# NGUYENLY.net
KiCad netlist of a schematic drawn in Altium Designer
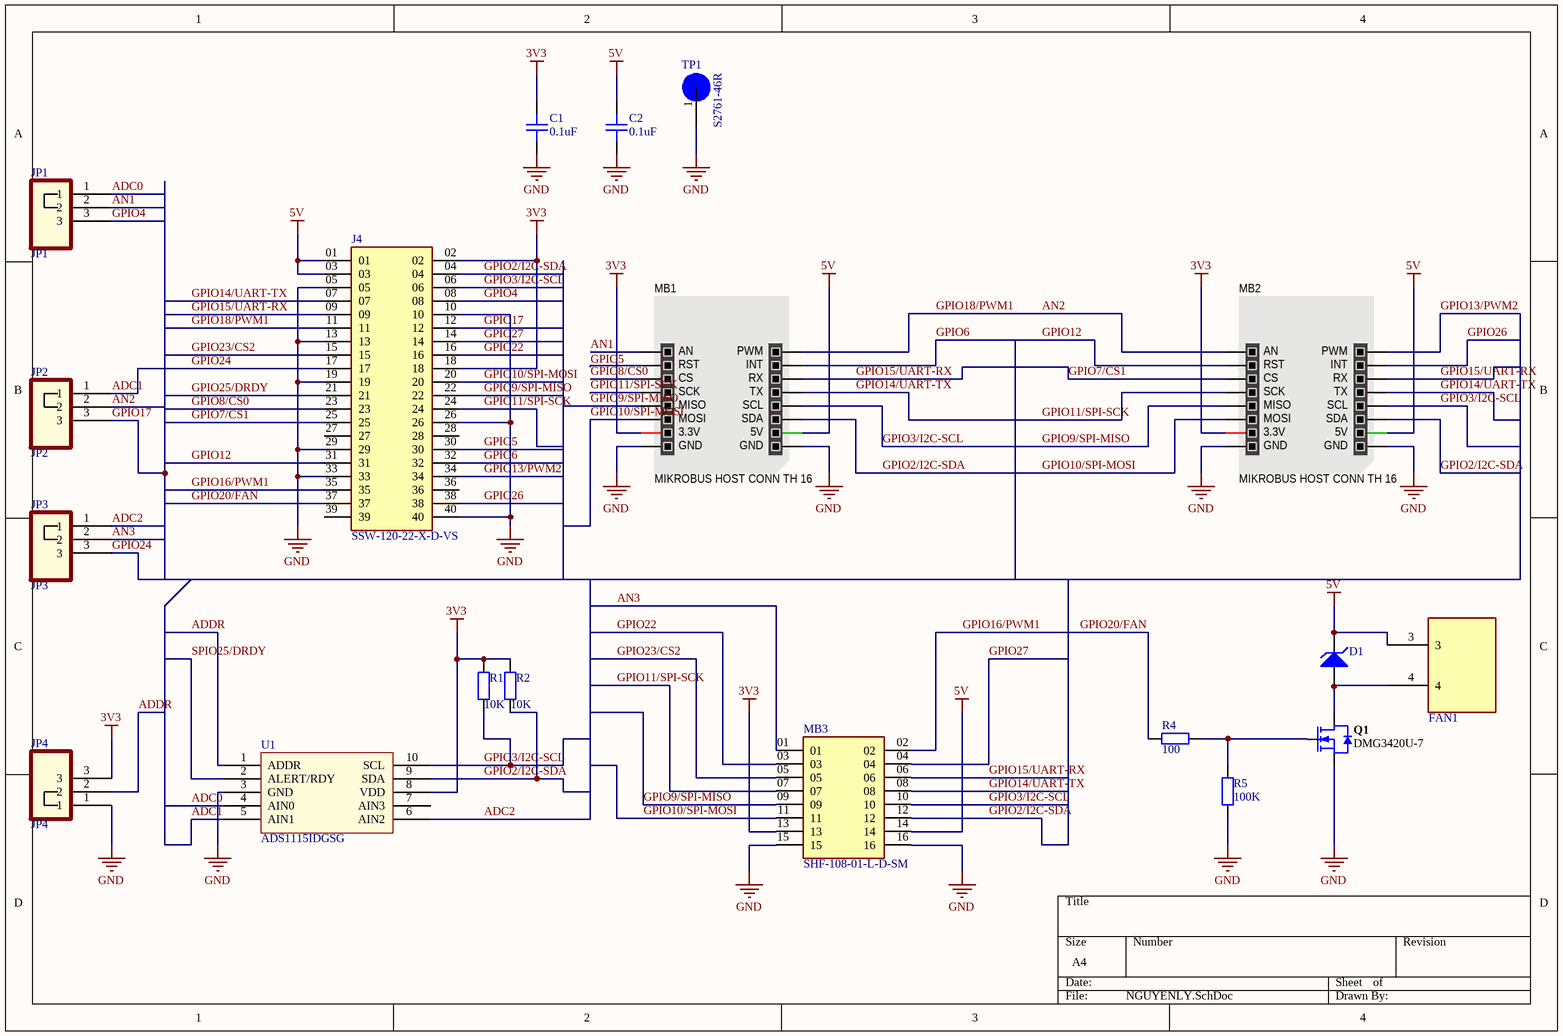
[diagram p0: NGUYENLY.SchDoc]

(export (version "E")
  (design (tool "Eeschema 10.0.6"))
  (components
    (comp (ref "C1")
      (value "0.1uF")
      (footprint "CAPC-0603 (1608)")
      (description "CAP SMD, Not Fill, 0603")
      (libsource (lib "BYTECH_HW_LIB_2019 (1) (1)") (part "CAPC NF 0603"))
    )
    (comp (ref "C2")
      (value "0.1uF")
      (footprint "CAPC-0603 (1608)")
      (description "CAP SMD, Not Fill, 0603")
      (libsource (lib "BYTECH_HW_LIB_2019 (1) (1)") (part "CAPC NF 0603"))
    )
    (comp (ref "D1")
      (value "Diode Zener 3v3 1.5w")
      (footprint "DIODE_DO214AC_SMA")
      (description "DIODE ZENER 3.3V 1.5W SMA, DO-214AC")
      (fields (field (name "MPN") "1SMA5913BT3G"))
      (libsource (lib "BYTECH_HW_LIB_2019 (1) (1)") (part "1SMA5913BT3G; BZG05C3V3TR"))
    )
    (comp (ref "FAN1")
      (value "MF30101V1-1000U-A99")
      (footprint "Sunon_Fans_0_MFG")
      (libsource (lib "UNK_Sunon_Fans_MF30101V1-1000U-A99_eec") (part "MF30101V1-1000U-A99"))
    )
    (comp (ref "J4")
      (value "SSW-120-22-X-D-VS")
      (footprint "SAMTEC_SSW-120-22-X-D-VS")
      (description "40 Position Receptacle Connector Surface Mount")
      (fields (field (name "MF") "Samtec") (field (name "MP") "SSW-120-22-G-D-VS"))
      (libsource (lib "SSW-120-22-X-D-VS") (part "SSW-120-22-X-D-VS"))
    )
    (comp (ref "JP1") (value "JP1") (footprint "PCB") (libsource (lib "JP1") (part "JP")))
    (comp (ref "JP2") (value "JP2") (footprint "PCB") (libsource (lib "JP1") (part "JP")))
    (comp (ref "JP3") (value "JP3") (footprint "PCB") (libsource (lib "JP1") (part "JP")))
    (comp (ref "JP4") (value "JP4") (footprint "PCB") (libsource (lib "") (part "JP_1")))
    (comp (ref "MB1")
      (value "MIKROBUS HOST CONN TH 16")
      (footprint "MIKROBUS HOST SMD 16 - Black")
      (libsource (lib "SOCKET mikroBUS 16 SMD") (part "MIKROBUS HOST CONN"))
    )
    (comp (ref "MB2")
      (value "MIKROBUS HOST CONN TH 16")
      (footprint "MIKROBUS HOST SMD 16 - Black")
      (libsource (lib "SOCKET mikroBUS 16 SMD") (part "MIKROBUS HOST CONN"))
    )
    (comp (ref "MB3")
      (value "SHF-108-01-L-D-SM")
      (footprint "SAMTEC_SHF-108-01-L-D-SM")
      (fields (field (name "MF") "Samtec"))
      (libsource (lib "SHF-108-01-L-D-SM") (part "SHF-108-01-L-D-SM"))
    )
    (comp (ref "Q1")
      (value "DMG3420U-7")
      (footprint "SOT23-123")
      (description "N-channel Enhancement Mode Field-effect Transistor")
      (libsource (lib "TechMT.VN_Lib_Project v2") (part "2N7002"))
    )
    (comp (ref "R1")
      (value "10K")
      (footprint "RESC-0603 (1608)")
      (description "RES SMD, Not Fill, 0603")
      (libsource (lib "") (part "RESC NF 0603_1"))
    )
    (comp (ref "R2")
      (value "10K")
      (footprint "RESC-0603 (1608)")
      (description "RES SMD, Not Fill, 0603")
      (libsource (lib "") (part "RESC NF 0603_1"))
    )
    (comp (ref "R4")
      (value "100")
      (footprint "RESC-0603 (1608)")
      (description "RES SMD, Not Fill, 0603")
      (libsource (lib "") (part "RESC NF 0603_2"))
    )
    (comp (ref "R5")
      (value "100K")
      (footprint "RESC-0603 (1608)")
      (description "RES SMD, Not Fill, 0603")
      (libsource (lib "BYTECH_HW_LIB_2019 (1) (1)") (part "RESC NF 0603"))
    )
    (comp (ref "TP1")
      (value "S2761-46R")
      (footprint "HARWIN_S2761-46R")
      (description "Natural PC Test Point Brass, Tin Plating Surface Mount Mounting Type")
      (fields (field (name "DIGI-KEY_PART_NUMBER") "952-2665-2-ND") (field (name "MF") "Harwin Inc."))
      (libsource (lib "TP1_S2761-46R") (part "S2761-46R"))
    )
    (comp (ref "U1")
      (value "ADS1115IDGSG")
      (footprint "ADS1115IDGSR")
      (libsource (lib "LeNgocHuyHoang") (part "ADS1115IDGSG"))
    )
  )
  (nets
    (net (code "1") (name "/ADC0") (class "Default")
      (node (ref "JP1") (pin "1") (pinfunction "1_1") (pintype "passive"))
      (node (ref "U1") (pin "4") (pinfunction "AIN0_4") (pintype "passive"))
    )
    (net (code "2") (name "/ADC1") (class "Default")
      (node (ref "J4") (pin "17") (pinfunction "17_17") (pintype "passive"))
      (node (ref "JP2") (pin "1") (pinfunction "1_1") (pintype "passive"))
      (node (ref "JP3") (pin "3") (pinfunction "3_3") (pintype "passive"))
      (node (ref "U1") (pin "5") (pinfunction "AIN1_5") (pintype "passive"))
    )
    (net (code "3") (name "/ADC2") (class "Default")
      (node (ref "JP3") (pin "1") (pinfunction "1_1") (pintype "passive"))
      (node (ref "U1") (pin "6") (pinfunction "AIN2_6") (pintype "passive"))
    )
    (net (code "4") (name "/ADDR") (class "Default")
      (node (ref "JP4") (pin "2") (pinfunction "2_2") (pintype "passive"))
      (node (ref "U1") (pin "1") (pinfunction "ADDR_1") (pintype "passive"))
    )
    (net (code "5") (name "/AN1") (class "Default")
      (node (ref "JP1") (pin "2") (pinfunction "2_2") (pintype "passive"))
      (node (ref "MB1") (pin "1") (pinfunction "AN_1") (pintype "passive"))
    )
    (net (code "6") (name "/AN2") (class "Default")
      (node (ref "J4") (pin "11") (pinfunction "11_11") (pintype "passive"))
      (node (ref "J4") (pin "15") (pinfunction "15_15") (pintype "passive"))
      (node (ref "J4") (pin "21") (pinfunction "21_21") (pintype "passive"))
      (node (ref "JP2") (pin "2") (pinfunction "2_2") (pintype "passive"))
      (node (ref "MB1") (pin "16") (pinfunction "PWM_16") (pintype "passive"))
      (node (ref "MB2") (pin "1") (pinfunction "AN_1") (pintype "passive"))
      (node (ref "MB3") (pin "05") (pinfunction "05_05") (pintype "passive"))
    )
    (net (code "7") (name "/AN3") (class "Default")
      (node (ref "JP3") (pin "2") (pinfunction "2_2") (pintype "passive"))
      (node (ref "MB3") (pin "01") (pinfunction "01_01") (pintype "passive"))
    )
    (net (code "8") (name "/GPIO10{slash}SPI-MOSI") (class "Default")
      (node (ref "J4") (pin "04") (pinfunction "04_04") (pintype "passive"))
      (node (ref "J4") (pin "06") (pinfunction "06_06") (pintype "passive"))
      (node (ref "J4") (pin "20") (pinfunction "20_20") (pintype "passive"))
      (node (ref "J4") (pin "22") (pinfunction "22_22") (pintype "passive"))
      (node (ref "MB1") (pin "11") (pinfunction "SDA_11") (pintype "passive"))
      (node (ref "MB1") (pin "12") (pinfunction "SCL_12") (pintype "passive"))
      (node (ref "MB1") (pin "5") (pinfunction "MISO_5") (pintype "passive"))
      (node (ref "MB1") (pin "6") (pinfunction "MOSI_6") (pintype "passive"))
      (node (ref "MB2") (pin "11") (pinfunction "SDA_11") (pintype "passive"))
      (node (ref "MB2") (pin "12") (pinfunction "SCL_12") (pintype "passive"))
      (node (ref "MB2") (pin "5") (pinfunction "MISO_5") (pintype "passive"))
      (node (ref "MB2") (pin "6") (pinfunction "MOSI_6") (pintype "passive"))
      (node (ref "MB3") (pin "09") (pinfunction "09_09") (pintype "passive"))
      (node (ref "MB3") (pin "10") (pinfunction "10_10") (pintype "passive"))
      (node (ref "MB3") (pin "11") (pinfunction "11_11") (pintype "passive"))
      (node (ref "MB3") (pin "12") (pinfunction "12_12") (pintype "passive"))
      (node (ref "R1") (pin "1") (pinfunction "1_1") (pintype "passive"))
      (node (ref "R2") (pin "1") (pinfunction "1_1") (pintype "passive"))
      (node (ref "U1") (pin "10") (pinfunction "SCL_10") (pintype "passive"))
      (node (ref "U1") (pin "9") (pinfunction "SDA_9") (pintype "passive"))
    )
    (net (code "9") (name "/GPIO11{slash}SPI-SCK") (class "Default")
      (node (ref "J4") (pin "07") (pinfunction "07_07") (pintype "passive"))
      (node (ref "J4") (pin "24") (pinfunction "24_24") (pintype "passive"))
      (node (ref "J4") (pin "30") (pinfunction "30_30") (pintype "passive"))
      (node (ref "MB1") (pin "13") (pinfunction "TX_13") (pintype "passive"))
      (node (ref "MB1") (pin "2") (pinfunction "RST_2") (pintype "passive"))
      (node (ref "MB1") (pin "4") (pinfunction "SCK_4") (pintype "passive"))
      (node (ref "MB2") (pin "13") (pinfunction "TX_13") (pintype "passive"))
      (node (ref "MB2") (pin "4") (pinfunction "SCK_4") (pintype "passive"))
      (node (ref "MB3") (pin "07") (pinfunction "07_07") (pintype "passive"))
      (node (ref "MB3") (pin "08") (pinfunction "08_08") (pintype "passive"))
    )
    (net (code "10") (name "/GPIO12") (class "Default")
      (node (ref "J4") (pin "08") (pinfunction "08_08") (pintype "passive"))
      (node (ref "J4") (pin "12") (pinfunction "12_12") (pintype "passive"))
      (node (ref "J4") (pin "31") (pinfunction "31_31") (pintype "passive"))
      (node (ref "J4") (pin "32") (pinfunction "32_32") (pintype "passive"))
      (node (ref "J4") (pin "34") (pinfunction "34_34") (pintype "passive"))
      (node (ref "J4") (pin "35") (pinfunction "35_35") (pintype "passive"))
      (node (ref "J4") (pin "37") (pinfunction "37_37") (pintype "passive"))
      (node (ref "JP1") (pin "3") (pinfunction "3_3") (pintype "passive"))
      (node (ref "JP2") (pin "3") (pinfunction "3_3") (pintype "passive"))
      (node (ref "MB1") (pin "15") (pinfunction "INT_15") (pintype "passive"))
      (node (ref "MB2") (pin "16") (pinfunction "PWM_16") (pintype "passive"))
      (node (ref "MB2") (pin "2") (pinfunction "RST_2") (pintype "passive"))
      (node (ref "MB3") (pin "02") (pinfunction "02_02") (pintype "passive"))
      (node (ref "R4") (pin "2") (pinfunction "2_2") (pintype "passive"))
    )
    (net (code "11") (name "/GPIO15{slash}UART-RX") (class "Default")
      (node (ref "J4") (pin "09") (pinfunction "09_09") (pintype "passive"))
      (node (ref "J4") (pin "23") (pinfunction "23_23") (pintype "passive"))
      (node (ref "J4") (pin "25") (pinfunction "25_25") (pintype "passive"))
      (node (ref "MB1") (pin "14") (pinfunction "RX_14") (pintype "passive"))
      (node (ref "MB1") (pin "3") (pinfunction "CS_3") (pintype "passive"))
      (node (ref "MB2") (pin "14") (pinfunction "RX_14") (pintype "passive"))
      (node (ref "MB2") (pin "3") (pinfunction "CS_3") (pintype "passive"))
      (node (ref "MB3") (pin "06") (pinfunction "06_06") (pintype "passive"))
    )
    (net (code "12") (name "/GPIO22") (class "Default")
      (node (ref "J4") (pin "16") (pinfunction "16_16") (pintype "passive"))
      (node (ref "MB3") (pin "03") (pinfunction "03_03") (pintype "passive"))
    )
    (net (code "13") (name "/GPIO26") (class "Default")
      (node (ref "J4") (pin "38") (pinfunction "38_38") (pintype "passive"))
      (node (ref "MB2") (pin "15") (pinfunction "INT_15") (pintype "passive"))
    )
    (net (code "14") (name "/GPIO27") (class "Default")
      (node (ref "J4") (pin "14") (pinfunction "14_14") (pintype "passive"))
      (node (ref "MB3") (pin "04") (pinfunction "04_04") (pintype "passive"))
    )
    (net (code "15") (name "/SPIO25{slash}DRDY") (class "Default")
      (node (ref "U1") (pin "2") (pinfunction "ALERT/RDY_2") (pintype "passive"))
    )
    (net (code "16") (name "3V3") (class "Default")
      (node (ref "C1") (pin "2") (pinfunction "2_2") (pintype "passive"))
      (node (ref "J4") (pin "02") (pinfunction "02_02") (pintype "passive"))
      (node (ref "J4") (pin "18") (pinfunction "18_18") (pintype "passive"))
      (node (ref "JP4") (pin "3") (pinfunction "3_3") (pintype "passive"))
      (node (ref "MB1") (pin "7") (pinfunction "3.3V_7") (pintype "passive"))
      (node (ref "MB2") (pin "7") (pinfunction "3.3V_7") (pintype "passive"))
      (node (ref "MB3") (pin "13") (pinfunction "13_13") (pintype "passive"))
      (node (ref "R1") (pin "2") (pinfunction "2_2") (pintype "passive"))
      (node (ref "R2") (pin "2") (pinfunction "2_2") (pintype "passive"))
      (node (ref "U1") (pin "8") (pinfunction "VDD_8") (pintype "passive"))
    )
    (net (code "17") (name "5V") (class "Default")
      (node (ref "C2") (pin "2") (pinfunction "2_2") (pintype "passive"))
      (node (ref "D1") (pin "2") (pinfunction "K_2") (pintype "passive"))
      (node (ref "FAN1") (pin "3") (pinfunction "3_3") (pintype "passive"))
      (node (ref "J4") (pin "01") (pinfunction "01_01") (pintype "passive"))
      (node (ref "J4") (pin "03") (pinfunction "03_03") (pintype "passive"))
      (node (ref "MB1") (pin "10") (pinfunction "5V_10") (pintype "passive"))
      (node (ref "MB2") (pin "10") (pinfunction "5V_10") (pintype "passive"))
      (node (ref "MB3") (pin "14") (pinfunction "14_14") (pintype "passive"))
    )
    (net (code "18") (name "GND") (class "Default")
      (node (ref "C1") (pin "1") (pinfunction "1_1") (pintype "passive"))
      (node (ref "C2") (pin "1") (pinfunction "1_1") (pintype "passive"))
      (node (ref "J4") (pin "05") (pinfunction "05_05") (pintype "passive"))
      (node (ref "J4") (pin "10") (pinfunction "10_10") (pintype "passive"))
      (node (ref "J4") (pin "13") (pinfunction "13_13") (pintype "passive"))
      (node (ref "J4") (pin "19") (pinfunction "19_19") (pintype "passive"))
      (node (ref "J4") (pin "26") (pinfunction "26_26") (pintype "passive"))
      (node (ref "J4") (pin "29") (pinfunction "29_29") (pintype "passive"))
      (node (ref "J4") (pin "33") (pinfunction "33_33") (pintype "passive"))
      (node (ref "J4") (pin "40") (pinfunction "40_40") (pintype "passive"))
      (node (ref "JP4") (pin "1") (pinfunction "1_1") (pintype "passive"))
      (node (ref "MB1") (pin "8") (pinfunction "GND_8") (pintype "passive"))
      (node (ref "MB1") (pin "9") (pinfunction "GND_9") (pintype "passive"))
      (node (ref "MB2") (pin "8") (pinfunction "GND_8") (pintype "passive"))
      (node (ref "MB2") (pin "9") (pinfunction "GND_9") (pintype "passive"))
      (node (ref "MB3") (pin "15") (pinfunction "15_15") (pintype "passive"))
      (node (ref "MB3") (pin "16") (pinfunction "16_16") (pintype "passive"))
      (node (ref "Q1") (pin "3") (pinfunction "S_3") (pintype "passive"))
      (node (ref "R5") (pin "2") (pinfunction "2_2") (pintype "passive"))
      (node (ref "TP1") (pin "1") (pinfunction "1_1") (pintype "passive"))
      (node (ref "U1") (pin "3") (pinfunction "GND_3") (pintype "passive"))
    )
    (net (code "19") (name "Net-(D1-A)") (class "Default")
      (node (ref "D1") (pin "1") (pinfunction "A_1") (pintype "passive"))
      (node (ref "FAN1") (pin "4") (pinfunction "4_4") (pintype "passive"))
      (node (ref "Q1") (pin "2") (pinfunction "D_2") (pintype "passive"))
    )
    (net (code "20") (name "Net-(Q1-G)") (class "Default")
      (node (ref "Q1") (pin "1") (pinfunction "G_1") (pintype "passive"))
      (node (ref "R4") (pin "1") (pinfunction "1_1") (pintype "passive"))
      (node (ref "R5") (pin "1") (pinfunction "1_1") (pintype "passive"))
    )
    (net (code "21") (name "unconnected-(J4-Pad27)") (class "Default")
      (node (ref "J4") (pin "27") (pinfunction "27_27") (pintype "passive"))
    )
    (net (code "22") (name "unconnected-(J4-Pad28)") (class "Default")
      (node (ref "J4") (pin "28") (pinfunction "28_28") (pintype "passive"))
    )
    (net (code "23") (name "unconnected-(J4-Pad36)") (class "Default")
      (node (ref "J4") (pin "36") (pinfunction "36_36") (pintype "passive"))
    )
    (net (code "24") (name "unconnected-(J4-Pad39)") (class "Default")
      (node (ref "J4") (pin "39") (pinfunction "39_39") (pintype "passive"))
    )
    (net (code "25") (name "unconnected-(U1-AIN3-Pad7)") (class "Default")
      (node (ref "U1") (pin "7") (pinfunction "AIN3_7") (pintype "passive"))
    )
  )
)
